# deBug.net
KiCad netlist of a schematic drawn in EAGLE
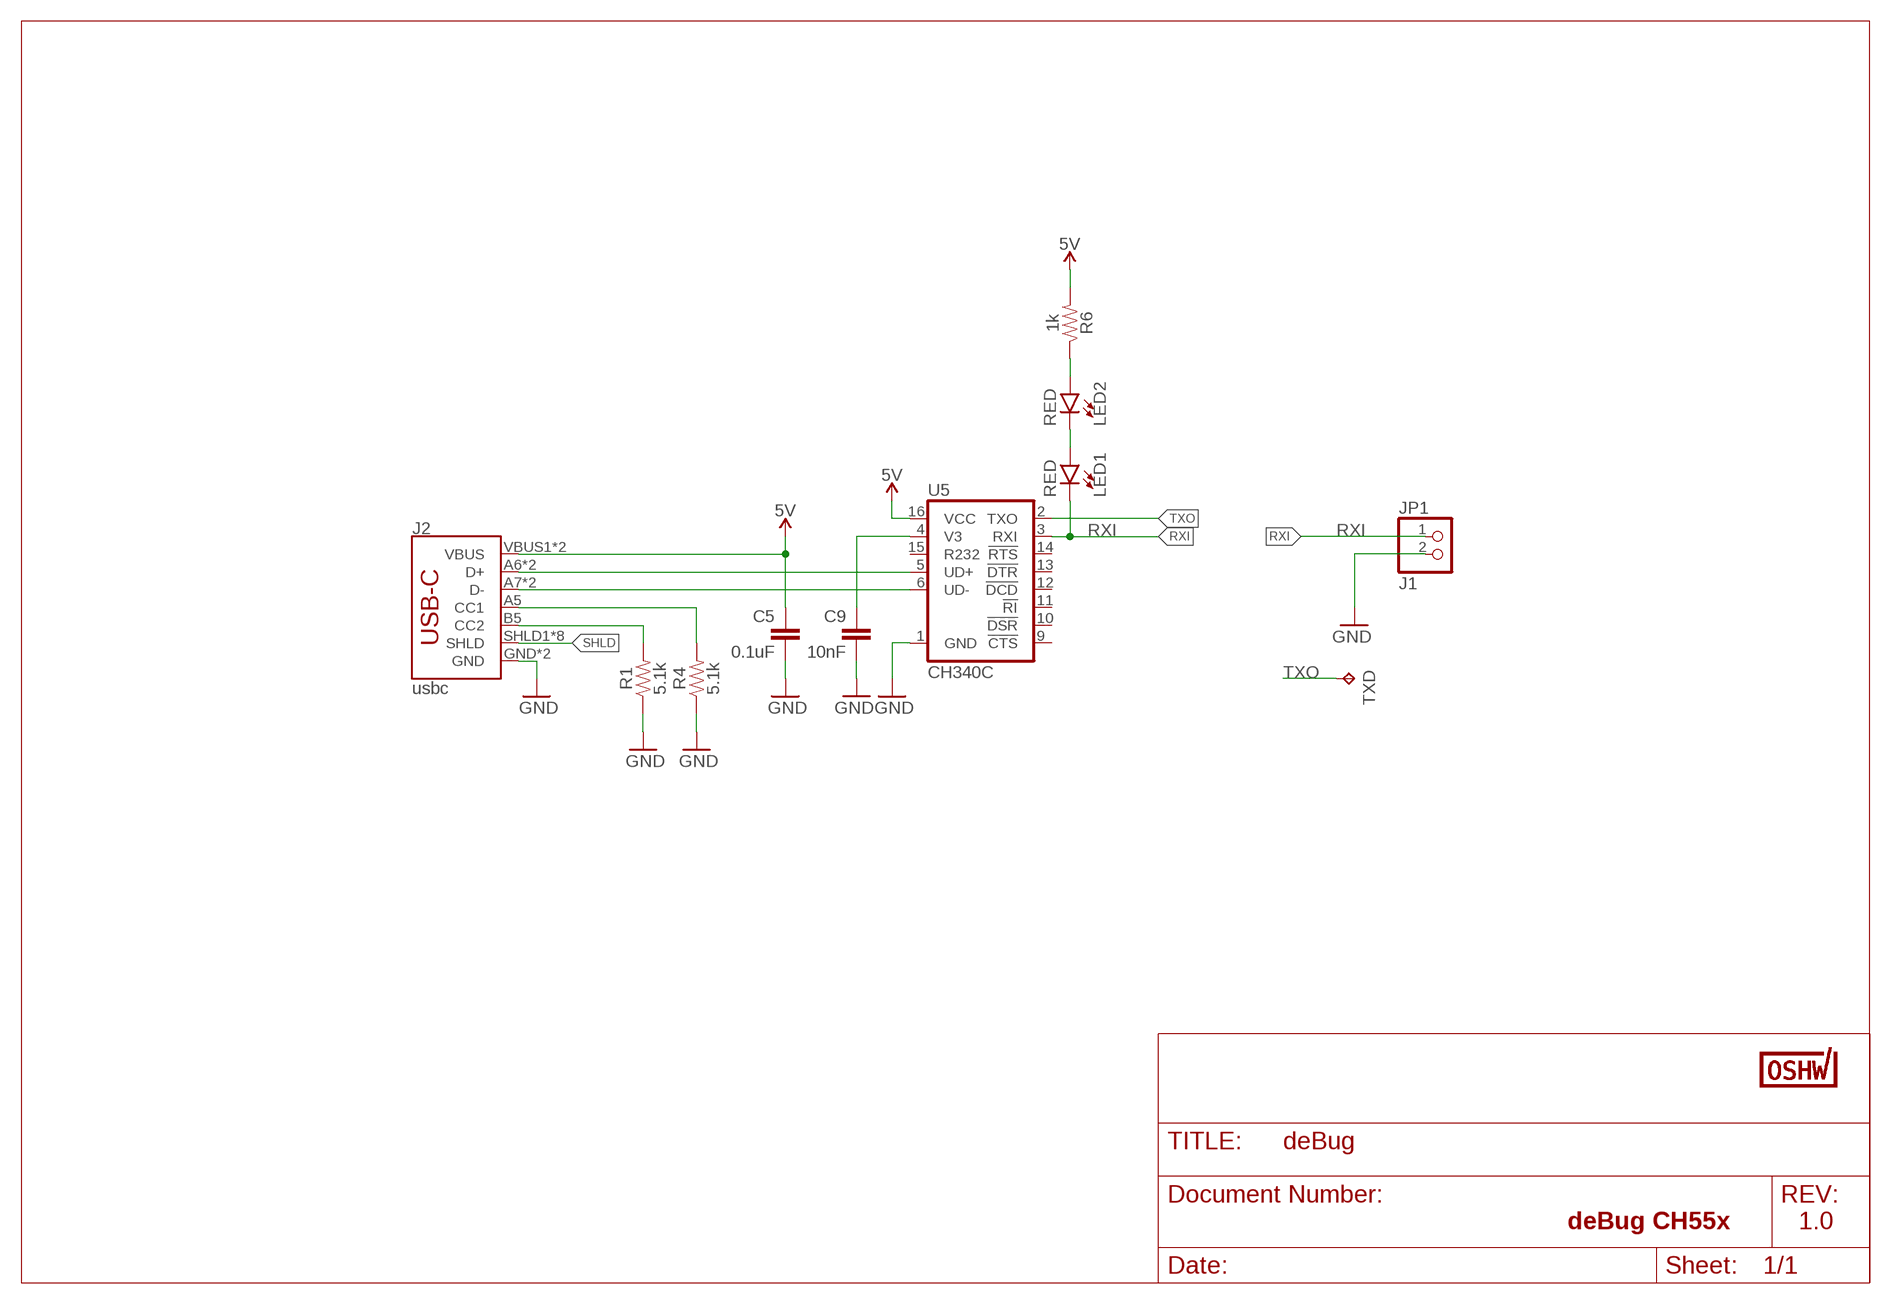
[diagram p0: schematic, sheet 1]

(export (version "E")
  (design (tool "Eeschema 10.0.6"))
  (components
    (comp (ref "C5")
      (value "0.1uF")
      (footprint "eagle-import:0603")
      (libsource (lib "eagle-import") (part "0.1UF-0603-25V-(+80/-20%)"))
    )
    (comp (ref "C9")
      (value "10nF")
      (footprint "eagle-import:0603")
      (libsource (lib "eagle-import") (part "10NF-0603-50V-10%"))
    )
    (comp (ref "J2")
      (value "usbc")
      (footprint "eagle-import:USB-C-16P")
      (libsource (lib "eagle-import") (part "USB_C16PIN"))
    )
    (comp (ref "JP1")
      (value "J1")
      (footprint "eagle-import:1X02")
      (libsource (lib "eagle-import") (part "PINHD-1X2"))
    )
    (comp (ref "LED1")
      (value "RED")
      (footprint "eagle-import:LED-0603")
      (libsource (lib "eagle-import") (part "LED-GREEN0603"))
    )
    (comp (ref "LED2")
      (value "RED")
      (footprint "eagle-import:LED-0603")
      (libsource (lib "eagle-import") (part "LED-GREEN0603"))
    )
    (comp (ref "R1")
      (value "5.1k")
      (footprint "eagle-import:0603")
      (libsource (lib "eagle-import") (part "5.1KOHM5.1KOHM-0603-1/10W-1%"))
    )
    (comp (ref "R4")
      (value "5.1k")
      (footprint "eagle-import:0603")
      (libsource (lib "eagle-import") (part "5.1KOHM5.1KOHM-0603-1/10W-1%"))
    )
    (comp (ref "R6")
      (value "1k")
      (footprint "eagle-import:0603")
      (libsource (lib "eagle-import") (part "1KOHM-0603-1/10W-1%"))
    )
    (comp (ref "TXD")
      (value "TPB1,27")
      (footprint "eagle-import:B1,27")
      (libsource (lib "eagle-import") (part "TPB1,27"))
    )
    (comp (ref "U$2")
      (value "CERT-LARGE")
      (footprint "eagle-import:CERT-LARGE-SILK")
      (libsource (lib "eagle-import") (part "CERT-LARGE"))
    )
    (comp (ref "U5")
      (value "CH340C")
      (footprint "eagle-import:SO016")
      (libsource (lib "eagle-import") (part "CH340C"))
    )
  )
  (nets
    (net (code "1") (name "5V") (class "Default")
      (node (ref "C5") (pin "1") (pinfunction "1_1") (pintype "passive"))
      (node (ref "J2") (pin "VBUS1") (pinfunction "VBUS_VBUS1") (pintype "bidirectional"))
      (node (ref "J2") (pin "VBUS2") (pinfunction "VBUS_VBUS2") (pintype "bidirectional"))
      (node (ref "R6") (pin "2") (pinfunction "2_2") (pintype "passive"))
      (node (ref "U5") (pin "16") (pinfunction "VCC_16") (pintype "bidirectional"))
    )
    (net (code "2") (name "GND") (class "Default")
      (node (ref "C5") (pin "2") (pinfunction "2_2") (pintype "passive"))
      (node (ref "C9") (pin "2") (pinfunction "2_2") (pintype "passive"))
      (node (ref "J2") (pin "GND") (pinfunction "GND_GND") (pintype "bidirectional"))
      (node (ref "J2") (pin "GND2") (pinfunction "GND_GND2") (pintype "bidirectional"))
      (node (ref "JP1") (pin "2") (pinfunction "2_2") (pintype "passive"))
      (node (ref "R1") (pin "1") (pinfunction "1_1") (pintype "passive"))
      (node (ref "R4") (pin "1") (pinfunction "1_1") (pintype "passive"))
      (node (ref "U5") (pin "1") (pinfunction "GND_1") (pintype "bidirectional"))
    )
    (net (code "3") (name "Net-(J2-CC1)") (class "Default")
      (node (ref "J2") (pin "A5") (pinfunction "CC1_A5") (pintype "bidirectional"))
      (node (ref "R4") (pin "2") (pinfunction "2_2") (pintype "passive"))
    )
    (net (code "4") (name "Net-(J2-CC2)") (class "Default")
      (node (ref "J2") (pin "B5") (pinfunction "CC2_B5") (pintype "bidirectional"))
      (node (ref "R1") (pin "2") (pinfunction "2_2") (pintype "passive"))
    )
    (net (code "5") (name "Net-(LED1-PadA)") (class "Default")
      (node (ref "LED1") (pin "A") (pinfunction "A_A") (pintype "passive"))
      (node (ref "LED2") (pin "C") (pinfunction "C_C") (pintype "passive"))
    )
    (net (code "6") (name "Net-(LED2-PadA)") (class "Default")
      (node (ref "LED2") (pin "A") (pinfunction "A_A") (pintype "passive"))
      (node (ref "R6") (pin "1") (pinfunction "1_1") (pintype "passive"))
    )
    (net (code "7") (name "Net-(U5-UD+)") (class "Default")
      (node (ref "J2") (pin "A6") (pinfunction "D+_A6") (pintype "bidirectional"))
      (node (ref "J2") (pin "B6") (pinfunction "D+_B6") (pintype "bidirectional"))
      (node (ref "U5") (pin "5") (pinfunction "UD+_5") (pintype "bidirectional"))
    )
    (net (code "8") (name "Net-(U5-UD-)") (class "Default")
      (node (ref "J2") (pin "A7") (pinfunction "D-_A7") (pintype "bidirectional"))
      (node (ref "J2") (pin "B7") (pinfunction "D-_B7") (pintype "bidirectional"))
      (node (ref "U5") (pin "6") (pinfunction "UD-_6") (pintype "bidirectional"))
    )
    (net (code "9") (name "Net-(U5-V3)") (class "Default")
      (node (ref "C9") (pin "1") (pinfunction "1_1") (pintype "passive"))
      (node (ref "U5") (pin "4") (pinfunction "V3_4") (pintype "bidirectional"))
    )
    (net (code "10") (name "RXI") (class "Default")
      (node (ref "JP1") (pin "1") (pinfunction "1_1") (pintype "passive"))
      (node (ref "LED1") (pin "C") (pinfunction "C_C") (pintype "passive"))
      (node (ref "U5") (pin "3") (pinfunction "RXI_3") (pintype "bidirectional"))
    )
    (net (code "11") (name "SHLD") (class "Default")
      (node (ref "J2") (pin "SHLD1") (pinfunction "SHLD_SHLD1") (pintype "bidirectional"))
      (node (ref "J2") (pin "SHLD2") (pinfunction "SHLD_SHLD2") (pintype "bidirectional"))
      (node (ref "J2") (pin "SHLD3") (pinfunction "SHLD_SHLD3") (pintype "bidirectional"))
      (node (ref "J2") (pin "SHLD4") (pinfunction "SHLD_SHLD4") (pintype "bidirectional"))
      (node (ref "J2") (pin "SHLD5") (pinfunction "SHLD_SHLD5") (pintype "bidirectional"))
      (node (ref "J2") (pin "SHLD6") (pinfunction "SHLD_SHLD6") (pintype "bidirectional"))
      (node (ref "J2") (pin "SHLD7") (pinfunction "SHLD_SHLD7") (pintype "bidirectional"))
      (node (ref "J2") (pin "SHLD8") (pinfunction "SHLD_SHLD8") (pintype "bidirectional"))
    )
    (net (code "12") (name "TXO") (class "Default")
      (node (ref "TXD") (pin "TP") (pinfunction "TP_TP") (pintype "input"))
      (node (ref "U5") (pin "2") (pinfunction "TXO_2") (pintype "bidirectional"))
    )
    (net (code "13") (name "unconnected-(U5-R232-Pad15)") (class "Default")
      (node (ref "U5") (pin "15") (pinfunction "R232_15") (pintype "bidirectional"))
    )
    (net (code "14") (name "unconnected-(U5-~{CTS}-Pad9)") (class "Default")
      (node (ref "U5") (pin "9") (pinfunction "~{CTS}_9") (pintype "bidirectional"))
    )
    (net (code "15") (name "unconnected-(U5-~{DCD}-Pad12)") (class "Default")
      (node (ref "U5") (pin "12") (pinfunction "~{DCD}_12") (pintype "bidirectional"))
    )
    (net (code "16") (name "unconnected-(U5-~{DSR}-Pad10)") (class "Default")
      (node (ref "U5") (pin "10") (pinfunction "~{DSR}_10") (pintype "bidirectional"))
    )
    (net (code "17") (name "unconnected-(U5-~{DTR}-Pad13)") (class "Default")
      (node (ref "U5") (pin "13") (pinfunction "~{DTR}_13") (pintype "bidirectional"))
    )
    (net (code "18") (name "unconnected-(U5-~{RI}-Pad11)") (class "Default")
      (node (ref "U5") (pin "11") (pinfunction "~{RI}_11") (pintype "bidirectional"))
    )
    (net (code "19") (name "unconnected-(U5-~{RTS}-Pad14)") (class "Default")
      (node (ref "U5") (pin "14") (pinfunction "~{RTS}_14") (pintype "bidirectional"))
    )
  )
)
